# Power.net
KiCad netlist of a schematic drawn in Altium Designer
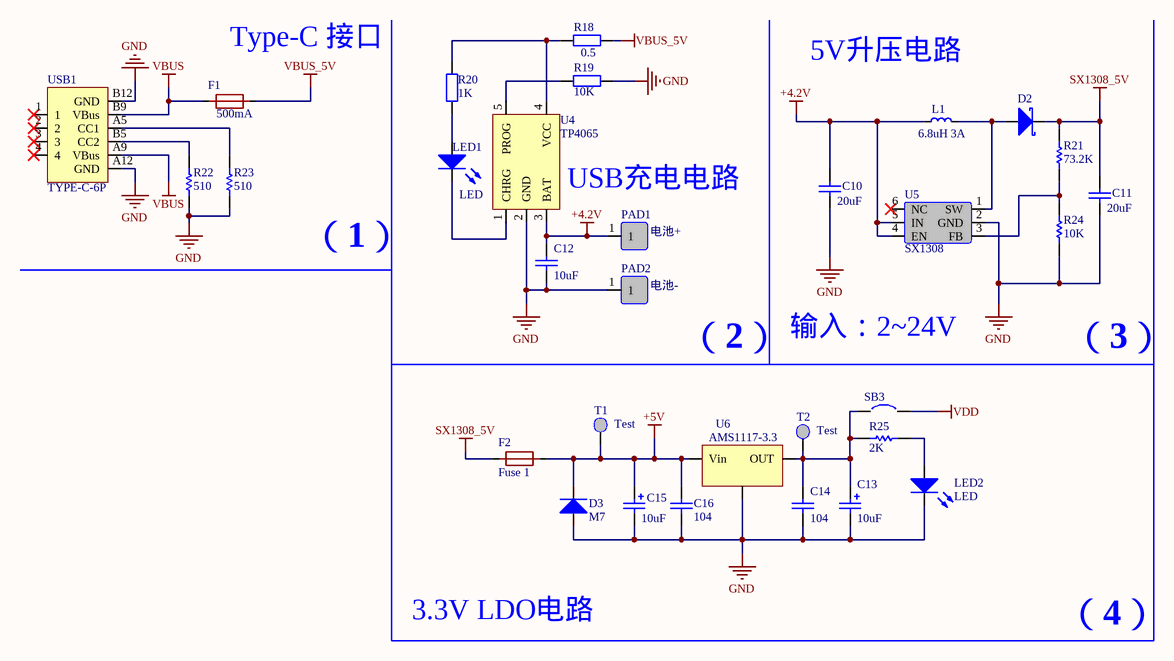
[diagram p0: Power.SchDoc]

(export (version "E")
  (design (tool "Eeschema 10.0.6"))
  (components
    (comp (ref "C10")
      (value "20uF")
      (footprint "C1210")
      (description "无极性电容")
      (fields (field (name "Comment") "Cap") (field (name "PUBLISHER") "信念D力量"))
      (libsource (lib "ZSF-90") (part "Cap"))
    )
    (comp (ref "C11")
      (value "20uF")
      (footprint "C1210")
      (description "无极性电容")
      (fields (field (name "Comment") "Cap") (field (name "PUBLISHER") "信念D力量"))
      (libsource (lib "ZSF-90") (part "Cap"))
    )
    (comp (ref "C12")
      (value "10uF")
      (footprint "C0603")
      (description "无极性电容")
      (fields (field (name "Comment") "Cap") (field (name "PUBLISHER") "信念D力量"))
      (libsource (lib "ZSF-90") (part "Cap"))
    )
    (comp (ref "C13")
      (value "10uF")
      (footprint "CASE-A_3216")
      (description "有极性电容")
      (fields (field (name "Comment") "Cap Pol1") (field (name "PUBLISHER") "信念D力量"))
      (libsource (lib "ZSF-90") (part "Cap Pol1"))
    )
    (comp (ref "C14")
      (value "104")
      (footprint "C0603")
      (description "无极性电容")
      (fields (field (name "Comment") "Cap") (field (name "PUBLISHER") "信念D力量"))
      (libsource (lib "ZSF-90") (part "Cap"))
    )
    (comp (ref "C15")
      (value "10uF")
      (footprint "CASE-A_3216")
      (description "有极性电容")
      (fields (field (name "Comment") "Cap Pol1") (field (name "PUBLISHER") "信念D力量"))
      (libsource (lib "ZSF-90") (part "Cap Pol1"))
    )
    (comp (ref "C16")
      (value "104")
      (footprint "C0603")
      (description "无极性电容")
      (fields (field (name "Comment") "Cap") (field (name "PUBLISHER") "信念D力量"))
      (libsource (lib "ZSF-90") (part "Cap"))
    )
    (comp (ref "D2")
      (value "D Schottky")
      (footprint "SMA_L4.4-W2.8-LS5.4-RD")
      (description "肖特基二极管")
      (fields (field (name "PUBLISHER") "Altium Limited"))
      (libsource (lib "ZSF-90") (part "D Schottky"))
    )
    (comp (ref "D3")
      (value "M7")
      (footprint "SOD-123_L2.8-W1.8-LS3.7-RD")
      (description "1N4007 二极管")
      (libsource (lib "ZSF-90") (part "1N4007"))
    )
    (comp (ref "F1")
      (value "500mA")
      (footprint "F0603")
      (description "保险丝 - Fuse")
      (libsource (lib "ZSF-90") (part "Fuse 1"))
    )
    (comp (ref "F2")
      (value "Fuse 1")
      (footprint "F0603")
      (description "保险丝 - Fuse")
      (libsource (lib "ZSF-90") (part "Fuse 1"))
    )
    (comp (ref "L1")
      (value "6.8uH 3A")
      (footprint "IND-SMD_L6.0-W6.0_SWPA6045S")
      (description "电感 - Inductor")
      (fields (field (name "Comment") "Inductor") (field (name "PUBLISHER") "Altium Limited"))
      (libsource (lib "ZSF-90") (part "Inductor"))
    )
    (comp (ref "LED1")
      (value "LED")
      (footprint "LED0603_RED")
      (description "发光二极管")
      (libsource (lib "ZSF-90") (part "LED"))
    )
    (comp (ref "LED2")
      (value "LED")
      (footprint "LED0603_RED")
      (description "发光二极管")
      (libsource (lib "ZSF-90") (part "LED"))
    )
    (comp (ref "PAD1") (value "电池+") (footprint "PAD_1") (libsource (lib "ZSF-90") (part "PAD_1")))
    (comp (ref "PAD2") (value "电池-") (footprint "PAD_1") (libsource (lib "ZSF-90") (part "PAD_1")))
    (comp (ref "R18")
      (value "0.5")
      (footprint "R0805")
      (description "欧盟电阻符号")
      (fields (field (name "Comment") "Res_EU"))
      (libsource (lib "ZSF-90") (part "Res_EU"))
    )
    (comp (ref "R19")
      (value "10K")
      (footprint "R0603")
      (description "欧盟电阻符号")
      (fields (field (name "Comment") "Res_EU"))
      (libsource (lib "ZSF-90") (part "Res_EU"))
    )
    (comp (ref "R20")
      (value "1K")
      (footprint "R0603")
      (description "欧盟电阻符号")
      (fields (field (name "Comment") "Res_EU"))
      (libsource (lib "") (part "Res_EU_1"))
    )
    (comp (ref "R21")
      (value "73.2K")
      (footprint "R0603")
      (description "美国电阻符号")
      (fields (field (name "Comment") "Res") (field (name "PUBLISHER") "Altium Limited"))
      (libsource (lib "ZSF-90") (part "Res"))
    )
    (comp (ref "R22")
      (value "510")
      (footprint "R0603")
      (description "美国电阻符号")
      (fields (field (name "Comment") "Res") (field (name "PUBLISHER") "Altium Limited"))
      (libsource (lib "ZSF-90") (part "Res"))
    )
    (comp (ref "R23")
      (value "510")
      (footprint "R0603")
      (description "美国电阻符号")
      (fields (field (name "Comment") "Res") (field (name "PUBLISHER") "Altium Limited"))
      (libsource (lib "ZSF-90") (part "Res"))
    )
    (comp (ref "R24")
      (value "10K")
      (footprint "R0603")
      (description "美国电阻符号")
      (fields (field (name "Comment") "Res") (field (name "PUBLISHER") "Altium Limited"))
      (libsource (lib "ZSF-90") (part "Res"))
    )
    (comp (ref "R25")
      (value "2K")
      (footprint "R0603")
      (description "美国电阻符号")
      (fields (field (name "Comment") "Res") (field (name "PUBLISHER") "Altium Limited"))
      (libsource (lib "ZSF-90") (part "Res"))
    )
    (comp (ref "SB3")
      (value "Circuit Breaker")
      (footprint "JP2_SMD")
      (description "断路器 短路选择 - Circuit Breaker")
      (fields (field (name "PUBLISHER") "Altium Limited"))
      (libsource (lib "ZSF-90") (part "Circuit Breaker"))
    )
    (comp (ref "T1") (value "Test") (footprint "TEST-SMD") (libsource (lib "ZSF-90") (part "Test")))
    (comp (ref "T2") (value "Test") (footprint "TEST-SMD") (libsource (lib "ZSF-90") (part "Test")))
    (comp (ref "U4")
      (value "TP4065")
      (footprint "SOT-23-5L")
      (description "电池管理IC")
      (libsource (lib "ZSF-90") (part "TP4065"))
    )
    (comp (ref "U5")
      (value "SX1308")
      (footprint "SOT-23-6_L2.9-W1.6-P0.95-LS2.8-BR")
      (description "DC-DC电源芯片  DC-DC电源芯片 2V~24V")
      (libsource (lib "ZSF-90") (part "SX1308"))
    )
    (comp (ref "U6")
      (value "AMS1117-3.3")
      (footprint "SOT-223_L6.7-W3.5-P2.30-BR")
      (description "线性稳压芯片 - Voltage Regulator")
      (libsource (lib "ZSF-90") (part "AMS1117-3.3"))
    )
    (comp (ref "USB1")
      (value "TYPE-C-6P")
      (footprint "USB-C-SMD_6P")
      (description "Type-C USB，6P")
      (libsource (lib "ZSF-90") (part "TYPE-C-6P"))
    )
  )
  (nets
    (net (code "1") (name "+4.2V") (class "Default")
      (node (ref "C10") (pin "2") (pinfunction "2_2") (pintype "passive"))
      (node (ref "C12") (pin "2") (pinfunction "2_2") (pintype "passive"))
      (node (ref "L1") (pin "1") (pinfunction "1_1") (pintype "passive"))
      (node (ref "PAD1") (pin "1") (pinfunction "1_1") (pintype "passive"))
      (node (ref "U4") (pin "3") (pinfunction "BAT_3") (pintype "passive"))
      (node (ref "U5") (pin "4") (pinfunction "EN_4") (pintype "passive"))
      (node (ref "U5") (pin "5") (pinfunction "IN_5") (pintype "passive"))
    )
    (net (code "2") (name "+5V") (class "Default")
      (node (ref "C15") (pin "1") (pinfunction "1_1") (pintype "passive"))
      (node (ref "C16") (pin "2") (pinfunction "2_2") (pintype "passive"))
      (node (ref "D3") (pin "1") (pinfunction "K_1") (pintype "passive"))
      (node (ref "F2") (pin "2") (pinfunction "2_2") (pintype "passive"))
      (node (ref "T1") (pin "1") (pinfunction "TEST_1") (pintype "passive"))
      (node (ref "U6") (pin "3") (pinfunction "Vin_3") (pintype "passive"))
    )
    (net (code "3") (name "GND") (class "Default")
      (node (ref "C10") (pin "1") (pinfunction "1_1") (pintype "passive"))
      (node (ref "C11") (pin "1") (pinfunction "1_1") (pintype "passive"))
      (node (ref "C12") (pin "1") (pinfunction "1_1") (pintype "passive"))
      (node (ref "C13") (pin "2") (pinfunction "2_2") (pintype "passive"))
      (node (ref "C14") (pin "1") (pinfunction "1_1") (pintype "passive"))
      (node (ref "C15") (pin "2") (pinfunction "2_2") (pintype "passive"))
      (node (ref "C16") (pin "1") (pinfunction "1_1") (pintype "passive"))
      (node (ref "D3") (pin "2") (pinfunction "A_2") (pintype "passive"))
      (node (ref "LED2") (pin "2") (pinfunction "K_2") (pintype "passive"))
      (node (ref "PAD2") (pin "1") (pinfunction "1_1") (pintype "passive"))
      (node (ref "R19") (pin "1") (pinfunction "1_1") (pintype "passive"))
      (node (ref "R22") (pin "2") (pinfunction "2_2") (pintype "passive"))
      (node (ref "R23") (pin "2") (pinfunction "2_2") (pintype "passive"))
      (node (ref "R24") (pin "2") (pinfunction "2_2") (pintype "passive"))
      (node (ref "U4") (pin "2") (pinfunction "GND_2") (pintype "passive"))
      (node (ref "U5") (pin "2") (pinfunction "GND_2") (pintype "passive"))
      (node (ref "U6") (pin "1") (pinfunction "GND_1") (pintype "passive"))
      (node (ref "USB1") (pin "A12") (pinfunction "GND_A12") (pintype "passive"))
      (node (ref "USB1") (pin "B12") (pinfunction "GND_B12") (pintype "passive"))
    )
    (net (code "4") (name "Net-(D2-A)") (class "Default")
      (node (ref "D2") (pin "1") (pinfunction "A_1") (pintype "passive"))
      (node (ref "L1") (pin "2") (pinfunction "2_2") (pintype "passive"))
      (node (ref "U5") (pin "1") (pinfunction "SW_1") (pintype "passive"))
    )
    (net (code "5") (name "Net-(LED1-A)") (class "Default")
      (node (ref "LED1") (pin "1") (pinfunction "A_1") (pintype "passive"))
      (node (ref "R20") (pin "1") (pinfunction "1_1") (pintype "passive"))
    )
    (net (code "6") (name "Net-(LED1-K)") (class "Default")
      (node (ref "LED1") (pin "2") (pinfunction "K_2") (pintype "passive"))
      (node (ref "U4") (pin "1") (pinfunction "CHRG_1") (pintype "passive"))
    )
    (net (code "7") (name "Net-(LED2-A)") (class "Default")
      (node (ref "LED2") (pin "1") (pinfunction "A_1") (pintype "passive"))
      (node (ref "R25") (pin "1") (pinfunction "1_1") (pintype "passive"))
    )
    (net (code "8") (name "Net-(T2-TEST)") (class "Default")
      (node (ref "C13") (pin "1") (pinfunction "1_1") (pintype "passive"))
      (node (ref "C14") (pin "2") (pinfunction "2_2") (pintype "passive"))
      (node (ref "R25") (pin "2") (pinfunction "2_2") (pintype "passive"))
      (node (ref "SB3") (pin "1") (pinfunction "1_1") (pintype "passive"))
      (node (ref "T2") (pin "1") (pinfunction "TEST_1") (pintype "passive"))
      (node (ref "U6") (pin "2") (pinfunction "OUT_2") (pintype "passive"))
    )
    (net (code "9") (name "Net-(U4-PROG)") (class "Default")
      (node (ref "R19") (pin "2") (pinfunction "2_2") (pintype "passive"))
      (node (ref "U4") (pin "5") (pinfunction "PROG_5") (pintype "passive"))
    )
    (net (code "10") (name "Net-(U4-VCC)") (class "Default")
      (node (ref "R18") (pin "2") (pinfunction "2_2") (pintype "passive"))
      (node (ref "R20") (pin "2") (pinfunction "2_2") (pintype "passive"))
      (node (ref "U4") (pin "4") (pinfunction "VCC_4") (pintype "passive"))
    )
    (net (code "11") (name "Net-(U5-FB)") (class "Default")
      (node (ref "R21") (pin "2") (pinfunction "2_2") (pintype "passive"))
      (node (ref "R24") (pin "1") (pinfunction "1_1") (pintype "passive"))
      (node (ref "U5") (pin "3") (pinfunction "FB_3") (pintype "passive"))
    )
    (net (code "12") (name "Net-(USB1-CC1)") (class "Default")
      (node (ref "R23") (pin "1") (pinfunction "1_1") (pintype "passive"))
      (node (ref "USB1") (pin "A5") (pinfunction "CC1_A5") (pintype "passive"))
    )
    (net (code "13") (name "Net-(USB1-CC2)") (class "Default")
      (node (ref "R22") (pin "1") (pinfunction "1_1") (pintype "passive"))
      (node (ref "USB1") (pin "B5") (pinfunction "CC2_B5") (pintype "passive"))
    )
    (net (code "14") (name "SX1308_5V") (class "Default")
      (node (ref "C11") (pin "2") (pinfunction "2_2") (pintype "passive"))
      (node (ref "D2") (pin "2") (pinfunction "K_2") (pintype "passive"))
      (node (ref "F2") (pin "1") (pinfunction "1_1") (pintype "passive"))
      (node (ref "R21") (pin "1") (pinfunction "1_1") (pintype "passive"))
    )
    (net (code "15") (name "VBUS") (class "Default")
      (node (ref "F1") (pin "1") (pinfunction "1_1") (pintype "passive"))
      (node (ref "USB1") (pin "A9") (pinfunction "VBus_A9") (pintype "passive"))
      (node (ref "USB1") (pin "B9") (pinfunction "VBus_B9") (pintype "passive"))
    )
    (net (code "16") (name "VBUS_5V") (class "Default")
      (node (ref "F1") (pin "2") (pinfunction "2_2") (pintype "passive"))
      (node (ref "R18") (pin "1") (pinfunction "1_1") (pintype "passive"))
    )
    (net (code "17") (name "VDD") (class "Default")
      (node (ref "SB3") (pin "2") (pinfunction "2_2") (pintype "passive"))
    )
    (net (code "18") (name "unconnected-(U5-NC-Pad6)") (class "Default")
      (node (ref "U5") (pin "6") (pinfunction "NC_6") (pintype "passive+no_connect"))
    )
    (net (code "19") (name "unconnected-(USB1-Pad1)") (class "Default")
      (node (ref "USB1") (pin "1") (pinfunction "1_1") (pintype "passive+no_connect"))
    )
    (net (code "20") (name "unconnected-(USB1-Pad2)") (class "Default")
      (node (ref "USB1") (pin "2") (pinfunction "2_2") (pintype "passive+no_connect"))
    )
    (net (code "21") (name "unconnected-(USB1-Pad3)") (class "Default")
      (node (ref "USB1") (pin "3") (pinfunction "3_3") (pintype "passive+no_connect"))
    )
    (net (code "22") (name "unconnected-(USB1-Pad4)") (class "Default")
      (node (ref "USB1") (pin "4") (pinfunction "4_4") (pintype "passive+no_connect"))
    )
  )
)
